# Keg_Cop_-_Daisy_Chain.net
KiCad netlist of a schematic drawn in EAGLE
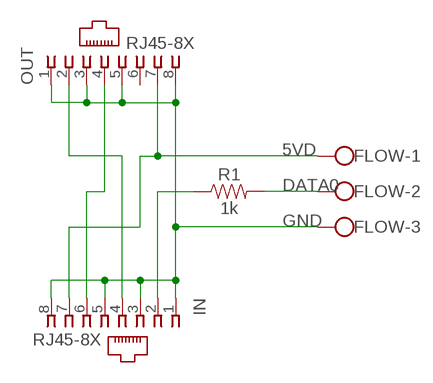
[diagram p0: schematic, sheet 1]

(export (version "E")
  (design (tool "Eeschema 10.0.6"))
  (components
    (comp (ref "FLOW")
      (value "W237-103")
      (footprint "eagle-import:W237-103")
      (fields (field (name "MPN") "237-103"))
      (libsource (lib "eagle-import") (part "W237-103"))
    )
    (comp (ref "IN")
      (value "RJ45-8X")
      (footprint "eagle-import:RJ45-NO-SHIELD")
      (libsource (lib "eagle-import") (part "RJ45-8X"))
    )
    (comp (ref "OUT")
      (value "RJ45-8X")
      (footprint "eagle-import:RJ45-NO-SHIELD")
      (libsource (lib "eagle-import") (part "RJ45-8X"))
    )
    (comp (ref "R1")
      (value "1k")
      (footprint "eagle-import:AXIAL-0.3")
      (libsource (lib "eagle-import") (part "1KOHM-HORIZ-1/4W-5%"))
    )
  )
  (nets
    (net (code "1") (name "/5VD") (class "Default")
      (node (ref "FLOW") (pin "1") (pinfunction "KL_1") (pintype "passive"))
      (node (ref "IN") (pin "7") (pinfunction "7_7") (pintype "passive"))
      (node (ref "OUT") (pin "7") (pinfunction "7_7") (pintype "passive"))
    )
    (net (code "2") (name "/DATA0") (class "Default")
      (node (ref "IN") (pin "2") (pinfunction "2_2") (pintype "passive"))
      (node (ref "R1") (pin "P$1") (pinfunction "1_P$1") (pintype "passive"))
    )
    (net (code "3") (name "/GND") (class "Default")
      (node (ref "FLOW") (pin "3") (pinfunction "KL_3") (pintype "passive"))
      (node (ref "IN") (pin "1") (pinfunction "1_1") (pintype "passive"))
      (node (ref "IN") (pin "3") (pinfunction "3_3") (pintype "passive"))
      (node (ref "IN") (pin "5") (pinfunction "5_5") (pintype "passive"))
      (node (ref "IN") (pin "8") (pinfunction "8_8") (pintype "passive"))
      (node (ref "OUT") (pin "1") (pinfunction "1_1") (pintype "passive"))
      (node (ref "OUT") (pin "3") (pinfunction "3_3") (pintype "passive"))
      (node (ref "OUT") (pin "5") (pinfunction "5_5") (pintype "passive"))
      (node (ref "OUT") (pin "8") (pinfunction "8_8") (pintype "passive"))
    )
    (net (code "4") (name "Net-(FLOWB-KL)") (class "Default")
      (node (ref "FLOW") (pin "2") (pinfunction "KL_2") (pintype "passive"))
      (node (ref "R1") (pin "P$2") (pinfunction "2_P$2") (pintype "passive"))
    )
    (net (code "5") (name "Net-(IN-Pad4)") (class "Default")
      (node (ref "IN") (pin "4") (pinfunction "4_4") (pintype "passive"))
      (node (ref "OUT") (pin "2") (pinfunction "2_2") (pintype "passive"))
    )
    (net (code "6") (name "Net-(IN-Pad6)") (class "Default")
      (node (ref "IN") (pin "6") (pinfunction "6_6") (pintype "passive"))
      (node (ref "OUT") (pin "4") (pinfunction "4_4") (pintype "passive"))
    )
    (net (code "7") (name "unconnected-(OUT-Pad6)") (class "Default")
      (node (ref "OUT") (pin "6") (pinfunction "6_6") (pintype "passive"))
    )
  )
)
